# SCH_vibration_matrix_element_2022-10-09.net
KiCad netlist of a schematic drawn in EasyEDA
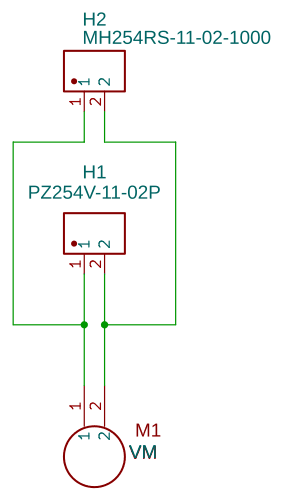
[diagram p0: schematic sheet]

(export (version "E")
  (design (tool "Eeschema 10.0.6"))
  (components
    (comp (ref "H1")
      (value "PZ254V-11-02P")
      (fields (field (name "BOM_Supplier Part") "C492401"))
      (libsource (lib "") (part "PZ254V-11-02P"))
    )
    (comp (ref "H2")
      (value "MH254RS-11-02-1000")
      (fields (field (name "BOM_Supplier Part") "C668122"))
      (libsource (lib "") (part "MH254RS-11-02-1000"))
    )
    (comp (ref "U1") (value "VM") (libsource (lib "") (part "VM")))
  )
  (nets
    (net (code "1") (name "Net-(H1-Pad1)") (class "Default")
      (node (ref "H1") (pin "1") (pinfunction "1_1") (pintype "unspecified"))
      (node (ref "H2") (pin "1") (pinfunction "1_1") (pintype "unspecified"))
      (node (ref "U1") (pin "1") (pinfunction "1_1") (pintype "unspecified"))
    )
    (net (code "2") (name "Net-(H1-Pad2)") (class "Default")
      (node (ref "H1") (pin "2") (pinfunction "2_2") (pintype "unspecified"))
      (node (ref "H2") (pin "2") (pinfunction "2_2") (pintype "unspecified"))
      (node (ref "U1") (pin "2") (pinfunction "2_2") (pintype "unspecified"))
    )
  )
)
